# Sheet_CL-SP-01.net
KiCad netlist of a schematic drawn in Altium Designer
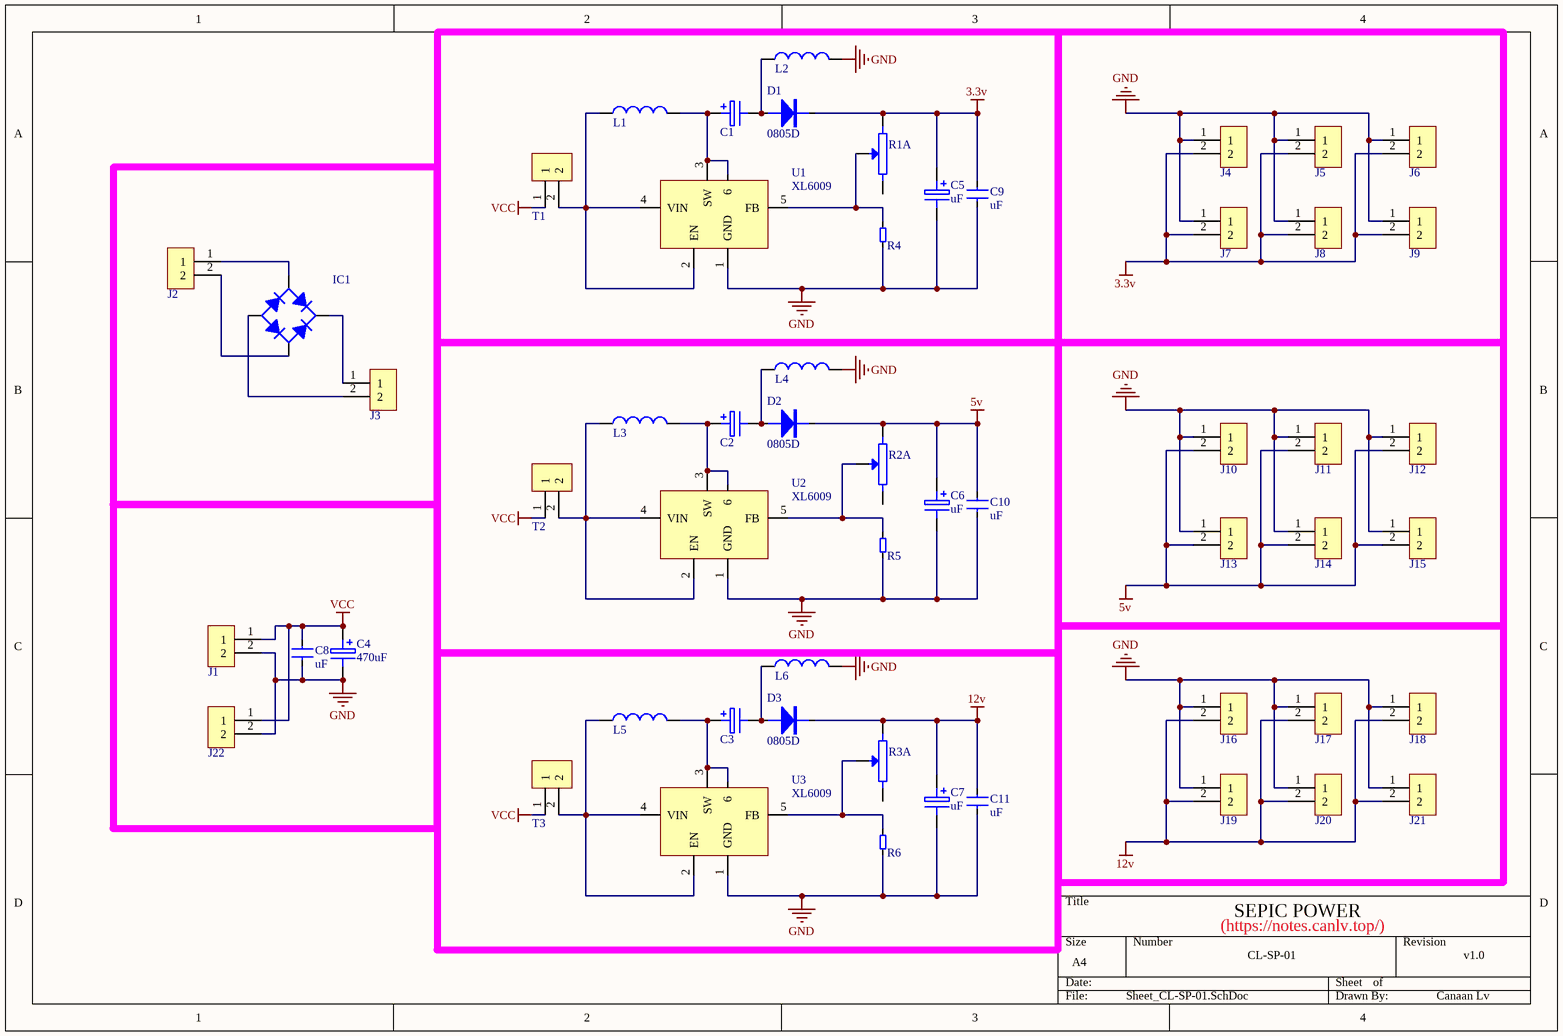
[diagram p0: Sheet_CL-SP-01.SchDoc]

(export (version "E")
  (design (tool "Eeschema 10.0.6"))
  (components
    (comp (ref "C1") (value "uF") (footprint "CZ0.60/50V47U") (libsource (lib "电容") (part "C直插电容")))
    (comp (ref "C2") (value "uF") (footprint "CZ0.60/50V47U") (libsource (lib "电容") (part "C直插电容")))
    (comp (ref "C3") (value "uF") (footprint "CZ0.60/50V47U") (libsource (lib "电容") (part "C直插电容")))
    (comp (ref "C4") (value "470uF") (footprint "CZ1.00/35V470uF") (libsource (lib "电容") (part "C直插电容")))
    (comp (ref "C5") (value "uF") (footprint "CZ0.65/25V100U") (libsource (lib "电容") (part "C直插电容")))
    (comp (ref "C6") (value "uF") (footprint "CZ0.65/25V100U") (libsource (lib "电容") (part "C直插电容")))
    (comp (ref "C7") (value "uF") (footprint "CZ0.65/25V100U") (libsource (lib "电容") (part "C直插电容")))
    (comp (ref "C8") (value "uF") (footprint "C1206") (libsource (lib "电容") (part "C贴片电容")))
    (comp (ref "C9") (value "uF") (footprint "C1206") (libsource (lib "电容") (part "C贴片电容")))
    (comp (ref "C10") (value "uF") (footprint "C1206") (libsource (lib "电容") (part "C贴片电容")))
    (comp (ref "C11") (value "uF") (footprint "C1206") (libsource (lib "电容") (part "C贴片电容")))
    (comp (ref "D1") (value "0805D") (footprint "0805D") (libsource (lib "二极管") (part "0805D")))
    (comp (ref "D2") (value "0805D") (footprint "0805D") (libsource (lib "二极管") (part "0805D")))
    (comp (ref "D3") (value "0805D") (footprint "0805D") (libsource (lib "二极管") (part "0805D")))
    (comp (ref "IC1") (value "~") (footprint "整流桥3") (libsource (lib "整流桥") (part "整流桥1")))
    (comp (ref "J1") (value "SIP-2") (footprint "2.54XH接插件2P") (libsource (lib "") (part "SIP-2_1")))
    (comp (ref "J2") (value "SIP-2") (footprint "2.54XH接插件2P") (libsource (lib "") (part "SIP-2_1")))
    (comp (ref "J3") (value "SIP-2") (footprint "2.54XH接插件2P") (libsource (lib "接插件") (part "SIP-2")))
    (comp (ref "J4") (value "SIP-2") (footprint "2.54XH接插件2P") (libsource (lib "接插件") (part "SIP-2")))
    (comp (ref "J5") (value "SIP-2") (footprint "2.54XH接插件2P") (libsource (lib "接插件") (part "SIP-2")))
    (comp (ref "J6") (value "SIP-2") (footprint "2.54XH接插件2P") (libsource (lib "接插件") (part "SIP-2")))
    (comp (ref "J7") (value "SIP-2") (footprint "2.54XH接插件2P") (libsource (lib "接插件") (part "SIP-2")))
    (comp (ref "J8") (value "SIP-2") (footprint "2.54XH接插件2P") (libsource (lib "接插件") (part "SIP-2")))
    (comp (ref "J9") (value "SIP-2") (footprint "2.54XH接插件2P") (libsource (lib "接插件") (part "SIP-2")))
    (comp (ref "J10") (value "SIP-2") (footprint "2.54XH接插件2P") (libsource (lib "接插件") (part "SIP-2")))
    (comp (ref "J11") (value "SIP-2") (footprint "2.54XH接插件2P") (libsource (lib "接插件") (part "SIP-2")))
    (comp (ref "J12") (value "SIP-2") (footprint "2.54XH接插件2P") (libsource (lib "接插件") (part "SIP-2")))
    (comp (ref "J13") (value "SIP-2") (footprint "2.54XH接插件2P") (libsource (lib "接插件") (part "SIP-2")))
    (comp (ref "J14") (value "SIP-2") (footprint "2.54XH接插件2P") (libsource (lib "接插件") (part "SIP-2")))
    (comp (ref "J15") (value "SIP-2") (footprint "2.54XH接插件2P") (libsource (lib "接插件") (part "SIP-2")))
    (comp (ref "J16") (value "SIP-2") (footprint "2.54XH接插件2P") (libsource (lib "接插件") (part "SIP-2")))
    (comp (ref "J17") (value "SIP-2") (footprint "2.54XH接插件2P") (libsource (lib "接插件") (part "SIP-2")))
    (comp (ref "J18") (value "SIP-2") (footprint "2.54XH接插件2P") (libsource (lib "接插件") (part "SIP-2")))
    (comp (ref "J19") (value "SIP-2") (footprint "2.54XH接插件2P") (libsource (lib "接插件") (part "SIP-2")))
    (comp (ref "J20") (value "SIP-2") (footprint "2.54XH接插件2P") (libsource (lib "接插件") (part "SIP-2")))
    (comp (ref "J21") (value "SIP-2") (footprint "2.54XH接插件2P") (libsource (lib "接插件") (part "SIP-2")))
    (comp (ref "J22") (value "SIP-2") (footprint "2.54XH接插件2P") (libsource (lib "") (part "SIP-2_1")))
    (comp (ref "L1") (value "贴片电感") (footprint "L5X5") (libsource (lib "电感") (part "贴片电感")))
    (comp (ref "L2") (value "贴片电感") (footprint "L5X5") (libsource (lib "电感") (part "贴片电感")))
    (comp (ref "L3") (value "贴片电感") (footprint "L5X5") (libsource (lib "电感") (part "贴片电感")))
    (comp (ref "L4") (value "贴片电感") (footprint "L5X5") (libsource (lib "电感") (part "贴片电感")))
    (comp (ref "L5") (value "贴片电感") (footprint "L5X5") (libsource (lib "电感") (part "贴片电感")))
    (comp (ref "L6") (value "贴片电感") (footprint "L5X5") (libsource (lib "电感") (part "贴片电感")))
    (comp (ref "R1") (value "主控") (footprint "ADJ-3296-1") (libsource (lib "电阻") (part "R电位器")))
    (comp (ref "R2") (value "主控") (footprint "ADJ-3296-1") (libsource (lib "电阻") (part "R电位器")))
    (comp (ref "R3") (value "主控") (footprint "ADJ-3296-1") (libsource (lib "电阻") (part "R电位器")))
    (comp (ref "R4") (value "R贴片电阻") (footprint "R1206") (libsource (lib "电阻") (part "R贴片电阻")))
    (comp (ref "R5") (value "R贴片电阻") (footprint "R1206") (libsource (lib "电阻") (part "R贴片电阻")))
    (comp (ref "R6") (value "R贴片电阻") (footprint "R1206") (libsource (lib "电阻") (part "R贴片电阻")))
    (comp (ref "T1") (value "SIP-2") (footprint "2.54排针1X2") (libsource (lib "") (part "SIP-2_2")))
    (comp (ref "T2") (value "SIP-2") (footprint "2.54排针1X2") (libsource (lib "") (part "SIP-2_2")))
    (comp (ref "T3") (value "SIP-2") (footprint "2.54排针1X2") (libsource (lib "") (part "SIP-2_2")))
    (comp (ref "U1")
      (value "XL6009")
      (footprint "TO-263-5")
      (description "Switching Power")
      (libsource (lib "General") (part "XL6009"))
    )
    (comp (ref "U2")
      (value "XL6009")
      (footprint "TO-263-5")
      (description "Switching Power")
      (libsource (lib "General") (part "XL6009"))
    )
    (comp (ref "U3")
      (value "XL6009")
      (footprint "TO-263-5")
      (description "Switching Power")
      (libsource (lib "General") (part "XL6009"))
    )
  )
  (nets
    (net (code "1") (name "3.3v") (class "Default")
      (node (ref "C5") (pin "1") (pinfunction "1_1") (pintype "passive"))
      (node (ref "C9") (pin "1") (pinfunction "1_1") (pintype "passive"))
      (node (ref "D1") (pin "K") (pinfunction "2_K") (pintype "passive"))
      (node (ref "J4") (pin "2") (pinfunction "2_2") (pintype "passive"))
      (node (ref "J5") (pin "2") (pinfunction "2_2") (pintype "passive"))
      (node (ref "J6") (pin "2") (pinfunction "2_2") (pintype "passive"))
      (node (ref "J7") (pin "2") (pinfunction "2_2") (pintype "passive"))
      (node (ref "J8") (pin "2") (pinfunction "2_2") (pintype "passive"))
      (node (ref "J9") (pin "2") (pinfunction "2_2") (pintype "passive"))
      (node (ref "R1") (pin "1") (pinfunction "1_1") (pintype "passive"))
    )
    (net (code "2") (name "5v") (class "Default")
      (node (ref "C10") (pin "1") (pinfunction "1_1") (pintype "passive"))
      (node (ref "C6") (pin "1") (pinfunction "1_1") (pintype "passive"))
      (node (ref "D2") (pin "K") (pinfunction "2_K") (pintype "passive"))
      (node (ref "J10") (pin "2") (pinfunction "2_2") (pintype "passive"))
      (node (ref "J11") (pin "2") (pinfunction "2_2") (pintype "passive"))
      (node (ref "J12") (pin "2") (pinfunction "2_2") (pintype "passive"))
      (node (ref "J13") (pin "2") (pinfunction "2_2") (pintype "passive"))
      (node (ref "J14") (pin "2") (pinfunction "2_2") (pintype "passive"))
      (node (ref "J15") (pin "2") (pinfunction "2_2") (pintype "passive"))
      (node (ref "R2") (pin "1") (pinfunction "1_1") (pintype "passive"))
    )
    (net (code "3") (name "12v") (class "Default")
      (node (ref "C11") (pin "1") (pinfunction "1_1") (pintype "passive"))
      (node (ref "C7") (pin "1") (pinfunction "1_1") (pintype "passive"))
      (node (ref "D3") (pin "K") (pinfunction "2_K") (pintype "passive"))
      (node (ref "J16") (pin "2") (pinfunction "2_2") (pintype "passive"))
      (node (ref "J17") (pin "2") (pinfunction "2_2") (pintype "passive"))
      (node (ref "J18") (pin "2") (pinfunction "2_2") (pintype "passive"))
      (node (ref "J19") (pin "2") (pinfunction "2_2") (pintype "passive"))
      (node (ref "J20") (pin "2") (pinfunction "2_2") (pintype "passive"))
      (node (ref "J21") (pin "2") (pinfunction "2_2") (pintype "passive"))
      (node (ref "R3") (pin "1") (pinfunction "1_1") (pintype "passive"))
    )
    (net (code "4") (name "GND") (class "Default")
      (node (ref "C10") (pin "2") (pinfunction "2_2") (pintype "passive"))
      (node (ref "C11") (pin "2") (pinfunction "2_2") (pintype "passive"))
      (node (ref "C4") (pin "2") (pinfunction "2_2") (pintype "passive"))
      (node (ref "C5") (pin "2") (pinfunction "2_2") (pintype "passive"))
      (node (ref "C6") (pin "2") (pinfunction "2_2") (pintype "passive"))
      (node (ref "C7") (pin "2") (pinfunction "2_2") (pintype "passive"))
      (node (ref "C8") (pin "2") (pinfunction "2_2") (pintype "passive"))
      (node (ref "C9") (pin "2") (pinfunction "2_2") (pintype "passive"))
      (node (ref "J1") (pin "2") (pinfunction "2_2") (pintype "passive"))
      (node (ref "J10") (pin "1") (pinfunction "1_1") (pintype "passive"))
      (node (ref "J11") (pin "1") (pinfunction "1_1") (pintype "passive"))
      (node (ref "J12") (pin "1") (pinfunction "1_1") (pintype "passive"))
      (node (ref "J13") (pin "1") (pinfunction "1_1") (pintype "passive"))
      (node (ref "J14") (pin "1") (pinfunction "1_1") (pintype "passive"))
      (node (ref "J15") (pin "1") (pinfunction "1_1") (pintype "passive"))
      (node (ref "J16") (pin "1") (pinfunction "1_1") (pintype "passive"))
      (node (ref "J17") (pin "1") (pinfunction "1_1") (pintype "passive"))
      (node (ref "J18") (pin "1") (pinfunction "1_1") (pintype "passive"))
      (node (ref "J19") (pin "1") (pinfunction "1_1") (pintype "passive"))
      (node (ref "J20") (pin "1") (pinfunction "1_1") (pintype "passive"))
      (node (ref "J21") (pin "1") (pinfunction "1_1") (pintype "passive"))
      (node (ref "J22") (pin "2") (pinfunction "2_2") (pintype "passive"))
      (node (ref "J4") (pin "1") (pinfunction "1_1") (pintype "passive"))
      (node (ref "J5") (pin "1") (pinfunction "1_1") (pintype "passive"))
      (node (ref "J6") (pin "1") (pinfunction "1_1") (pintype "passive"))
      (node (ref "J7") (pin "1") (pinfunction "1_1") (pintype "passive"))
      (node (ref "J8") (pin "1") (pinfunction "1_1") (pintype "passive"))
      (node (ref "J9") (pin "1") (pinfunction "1_1") (pintype "passive"))
      (node (ref "L2") (pin "2") (pinfunction "2_2") (pintype "passive"))
      (node (ref "L4") (pin "2") (pinfunction "2_2") (pintype "passive"))
      (node (ref "L6") (pin "2") (pinfunction "2_2") (pintype "passive"))
      (node (ref "R4") (pin "1") (pinfunction "1_1") (pintype "passive"))
      (node (ref "R5") (pin "1") (pinfunction "1_1") (pintype "passive"))
      (node (ref "R6") (pin "1") (pinfunction "1_1") (pintype "passive"))
      (node (ref "U1") (pin "1") (pinfunction "GND_1") (pintype "passive"))
      (node (ref "U2") (pin "1") (pinfunction "GND_1") (pintype "passive"))
      (node (ref "U3") (pin "1") (pinfunction "GND_1") (pintype "passive"))
    )
    (net (code "5") (name "Net-(D1-1)") (class "Default")
      (node (ref "C1") (pin "2") (pinfunction "2_2") (pintype "passive"))
      (node (ref "D1") (pin "A") (pinfunction "1_A") (pintype "passive"))
      (node (ref "L2") (pin "1") (pinfunction "1_1") (pintype "passive"))
    )
    (net (code "6") (name "Net-(D2-1)") (class "Default")
      (node (ref "C2") (pin "2") (pinfunction "2_2") (pintype "passive"))
      (node (ref "D2") (pin "A") (pinfunction "1_A") (pintype "passive"))
      (node (ref "L4") (pin "1") (pinfunction "1_1") (pintype "passive"))
    )
    (net (code "7") (name "Net-(D3-1)") (class "Default")
      (node (ref "C3") (pin "2") (pinfunction "2_2") (pintype "passive"))
      (node (ref "D3") (pin "A") (pinfunction "1_A") (pintype "passive"))
      (node (ref "L6") (pin "1") (pinfunction "1_1") (pintype "passive"))
    )
    (net (code "8") (name "Net-(IC1-+)") (class "Default")
      (node (ref "IC1") (pin "1") (pinfunction "+_1") (pintype "passive"))
      (node (ref "J3") (pin "1") (pinfunction "1_1") (pintype "passive"))
    )
    (net (code "9") (name "Net-(IC1--)") (class "Default")
      (node (ref "IC1") (pin "4") (pinfunction "-_4") (pintype "passive"))
      (node (ref "J3") (pin "2") (pinfunction "2_2") (pintype "passive"))
    )
    (net (code "10") (name "Net-(IC1-C-Pad2)") (class "Default")
      (node (ref "IC1") (pin "2") (pinfunction "C_2") (pintype "passive"))
      (node (ref "J2") (pin "1") (pinfunction "1_1") (pintype "passive"))
    )
    (net (code "11") (name "Net-(IC1-C-Pad3)") (class "Default")
      (node (ref "IC1") (pin "3") (pinfunction "C_3") (pintype "passive"))
      (node (ref "J2") (pin "2") (pinfunction "2_2") (pintype "passive"))
    )
    (net (code "12") (name "Net-(U1-EN)") (class "Default")
      (node (ref "L1") (pin "1") (pinfunction "1_1") (pintype "passive"))
      (node (ref "T1") (pin "2") (pinfunction "2_2") (pintype "passive"))
      (node (ref "U1") (pin "2") (pinfunction "EN_2") (pintype "passive"))
      (node (ref "U1") (pin "4") (pinfunction "VIN_4") (pintype "passive"))
    )
    (net (code "13") (name "Net-(U1-FB)") (class "Default")
      (node (ref "R1") (pin "2") (pinfunction "2_2") (pintype "passive"))
      (node (ref "R4") (pin "2") (pinfunction "2_2") (pintype "passive"))
      (node (ref "U1") (pin "5") (pinfunction "FB_5") (pintype "passive"))
    )
    (net (code "14") (name "Net-(U1-SW)") (class "Default")
      (node (ref "C1") (pin "1") (pinfunction "1_1") (pintype "passive"))
      (node (ref "L1") (pin "2") (pinfunction "2_2") (pintype "passive"))
      (node (ref "U1") (pin "3") (pinfunction "SW_3") (pintype "passive"))
      (node (ref "U1") (pin "6") (pinfunction "6_6") (pintype "passive"))
    )
    (net (code "15") (name "Net-(U2-EN)") (class "Default")
      (node (ref "L3") (pin "1") (pinfunction "1_1") (pintype "passive"))
      (node (ref "T2") (pin "2") (pinfunction "2_2") (pintype "passive"))
      (node (ref "U2") (pin "2") (pinfunction "EN_2") (pintype "passive"))
      (node (ref "U2") (pin "4") (pinfunction "VIN_4") (pintype "passive"))
    )
    (net (code "16") (name "Net-(U2-FB)") (class "Default")
      (node (ref "R2") (pin "2") (pinfunction "2_2") (pintype "passive"))
      (node (ref "R5") (pin "2") (pinfunction "2_2") (pintype "passive"))
      (node (ref "U2") (pin "5") (pinfunction "FB_5") (pintype "passive"))
    )
    (net (code "17") (name "Net-(U2-SW)") (class "Default")
      (node (ref "C2") (pin "1") (pinfunction "1_1") (pintype "passive"))
      (node (ref "L3") (pin "2") (pinfunction "2_2") (pintype "passive"))
      (node (ref "U2") (pin "3") (pinfunction "SW_3") (pintype "passive"))
      (node (ref "U2") (pin "6") (pinfunction "6_6") (pintype "passive"))
    )
    (net (code "18") (name "Net-(U3-EN)") (class "Default")
      (node (ref "L5") (pin "1") (pinfunction "1_1") (pintype "passive"))
      (node (ref "T3") (pin "2") (pinfunction "2_2") (pintype "passive"))
      (node (ref "U3") (pin "2") (pinfunction "EN_2") (pintype "passive"))
      (node (ref "U3") (pin "4") (pinfunction "VIN_4") (pintype "passive"))
    )
    (net (code "19") (name "Net-(U3-FB)") (class "Default")
      (node (ref "R3") (pin "2") (pinfunction "2_2") (pintype "passive"))
      (node (ref "R6") (pin "2") (pinfunction "2_2") (pintype "passive"))
      (node (ref "U3") (pin "5") (pinfunction "FB_5") (pintype "passive"))
    )
    (net (code "20") (name "Net-(U3-SW)") (class "Default")
      (node (ref "C3") (pin "1") (pinfunction "1_1") (pintype "passive"))
      (node (ref "L5") (pin "2") (pinfunction "2_2") (pintype "passive"))
      (node (ref "U3") (pin "3") (pinfunction "SW_3") (pintype "passive"))
      (node (ref "U3") (pin "6") (pinfunction "6_6") (pintype "passive"))
    )
    (net (code "21") (name "VCC") (class "Default")
      (node (ref "C4") (pin "1") (pinfunction "1_1") (pintype "passive"))
      (node (ref "C8") (pin "1") (pinfunction "1_1") (pintype "passive"))
      (node (ref "J1") (pin "1") (pinfunction "1_1") (pintype "passive"))
      (node (ref "J22") (pin "1") (pinfunction "1_1") (pintype "passive"))
      (node (ref "T1") (pin "1") (pinfunction "1_1") (pintype "passive"))
      (node (ref "T2") (pin "1") (pinfunction "1_1") (pintype "passive"))
      (node (ref "T3") (pin "1") (pinfunction "1_1") (pintype "passive"))
    )
    (net (code "22") (name "unconnected-(R1-Pad3)") (class "Default")
      (node (ref "R1") (pin "3") (pinfunction "3_3") (pintype "passive"))
    )
    (net (code "23") (name "unconnected-(R2-Pad3)") (class "Default")
      (node (ref "R2") (pin "3") (pinfunction "3_3") (pintype "passive"))
    )
    (net (code "24") (name "unconnected-(R3-Pad3)") (class "Default")
      (node (ref "R3") (pin "3") (pinfunction "3_3") (pintype "passive"))
    )
  )
)
